# relay.net
KiCad netlist of a schematic drawn in EAGLE
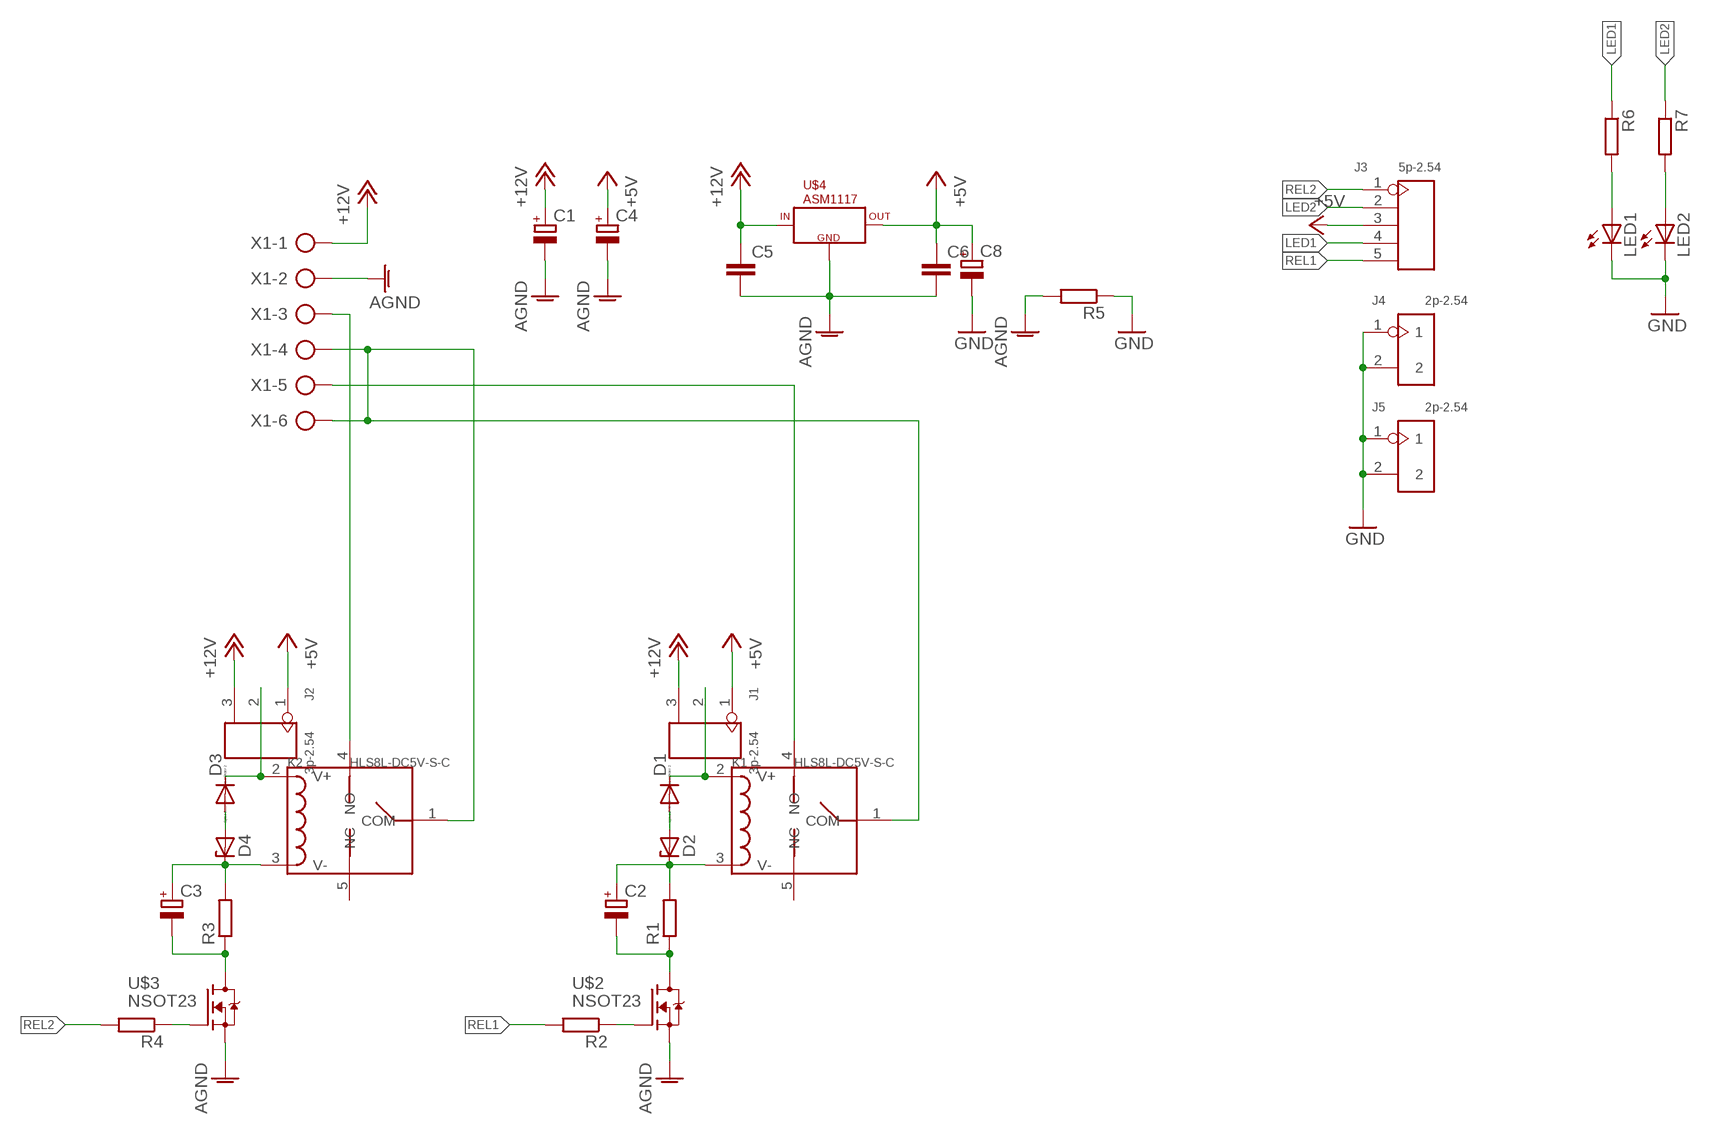
[diagram p0: schematic, sheet 1]

(export (version "E")
  (design (tool "Eeschema 10.0.6"))
  (components
    (comp (ref "C1")
      (value "CPOL-EU153CLV-0405")
      (footprint "eagle-import:153CLV-0405")
      (libsource (lib "eagle-import") (part "CPOL-EU153CLV-0405"))
    )
    (comp (ref "C2")
      (value "CPOL-EU153CLV-0405")
      (footprint "eagle-import:153CLV-0405")
      (libsource (lib "eagle-import") (part "CPOL-EU153CLV-0405"))
    )
    (comp (ref "C3")
      (value "CPOL-EU153CLV-0405")
      (footprint "eagle-import:153CLV-0405")
      (libsource (lib "eagle-import") (part "CPOL-EU153CLV-0405"))
    )
    (comp (ref "C4")
      (value "CPOL-EU153CLV-0405")
      (footprint "eagle-import:153CLV-0405")
      (libsource (lib "eagle-import") (part "CPOL-EU153CLV-0405"))
    )
    (comp (ref "C5")
      (value "C-EUC0805")
      (footprint "eagle-import:C0805")
      (libsource (lib "eagle-import") (part "C-EUC0805"))
    )
    (comp (ref "C6")
      (value "C-EUC0805")
      (footprint "eagle-import:C0805")
      (libsource (lib "eagle-import") (part "C-EUC0805"))
    )
    (comp (ref "C8")
      (value "CPOL-EUSMCD")
      (footprint "eagle-import:SMC_D")
      (libsource (lib "eagle-import") (part "CPOL-EUSMCD"))
    )
    (comp (ref "D1")
      (value "DIODE-MINIMELF")
      (footprint "eagle-import:MINIMELF")
      (libsource (lib "eagle-import") (part "DIODE-MINIMELF"))
    )
    (comp (ref "D2")
      (value "ZENER-DIODESOD80C")
      (footprint "eagle-import:SOD80C")
      (libsource (lib "eagle-import") (part "ZENER-DIODESOD80C"))
    )
    (comp (ref "D3")
      (value "DIODE-MINIMELF")
      (footprint "eagle-import:MINIMELF")
      (libsource (lib "eagle-import") (part "DIODE-MINIMELF"))
    )
    (comp (ref "D4")
      (value "ZENER-DIODESOD80C")
      (footprint "eagle-import:SOD80C")
      (libsource (lib "eagle-import") (part "ZENER-DIODESOD80C"))
    )
    (comp (ref "J1")
      (value "3p-2.54")
      (footprint "eagle-import:H3-2.54")
      (fields (field (name "MPN") "F185-1103A0BSYA1"))
      (libsource (lib "eagle-import") (part "DIP-BLACK-FEMALE-HEADER-VERT(3P-2.54)"))
    )
    (comp (ref "J2")
      (value "3p-2.54")
      (footprint "eagle-import:H3-2.54")
      (fields (field (name "MPN") "F185-1103A0BSYA1"))
      (libsource (lib "eagle-import") (part "DIP-BLACK-FEMALE-HEADER-VERT(3P-2.54)"))
    )
    (comp (ref "J3")
      (value "5p-2.54")
      (footprint "eagle-import:H5-2.54")
      (fields (field (name "MPN") "F185-1105A0BSYA1"))
      (libsource (lib "eagle-import") (part "DIP-BLACK-FEMALE-HEADER-VERT(5P-2.54)"))
    )
    (comp (ref "J4")
      (value "2p-2.54")
      (footprint "eagle-import:H2-2.54")
      (fields (field (name "MPN") "F185-1102A1BSYA1"))
      (libsource (lib "eagle-import") (part "DIP-BLACK-FEMALE-HEADER-VERT(2P-2.54)"))
    )
    (comp (ref "J5")
      (value "2p-2.54")
      (footprint "eagle-import:H2-2.54")
      (fields (field (name "MPN") "F185-1102A1BSYA1"))
      (libsource (lib "eagle-import") (part "DIP-BLACK-FEMALE-HEADER-VERT(2P-2.54)"))
    )
    (comp (ref "K1")
      (value "HLS8L-DC5V-S-C")
      (footprint "eagle-import:REY5-19.0X15.0X15.0MM")
      (libsource (lib "eagle-import") (part "RELAY-HLS8L-DC5V-S-C(5P-19X15MM)"))
    )
    (comp (ref "K2")
      (value "HLS8L-DC5V-S-C")
      (footprint "eagle-import:REY5-19.0X15.0X15.0MM")
      (libsource (lib "eagle-import") (part "RELAY-HLS8L-DC5V-S-C(5P-19X15MM)"))
    )
    (comp (ref "LED1")
      (value "LED5MM")
      (footprint "eagle-import:LED5MM")
      (libsource (lib "eagle-import") (part "LED5MM"))
    )
    (comp (ref "LED2")
      (value "LED5MM")
      (footprint "eagle-import:LED5MM")
      (libsource (lib "eagle-import") (part "LED5MM"))
    )
    (comp (ref "R1")
      (value "R-EU_R0805")
      (footprint "eagle-import:R0805")
      (libsource (lib "eagle-import") (part "R-EU_R0805"))
    )
    (comp (ref "R2")
      (value "R-EU_R0805")
      (footprint "eagle-import:R0805")
      (libsource (lib "eagle-import") (part "R-EU_R0805"))
    )
    (comp (ref "R3")
      (value "R-EU_R0805")
      (footprint "eagle-import:R0805")
      (libsource (lib "eagle-import") (part "R-EU_R0805"))
    )
    (comp (ref "R4")
      (value "R-EU_R0805")
      (footprint "eagle-import:R0805")
      (libsource (lib "eagle-import") (part "R-EU_R0805"))
    )
    (comp (ref "R5")
      (value "R-EU_R0805")
      (footprint "eagle-import:R0805")
      (libsource (lib "eagle-import") (part "R-EU_R0805"))
    )
    (comp (ref "R6")
      (value "R-EU_R0805")
      (footprint "eagle-import:R0805")
      (libsource (lib "eagle-import") (part "R-EU_R0805"))
    )
    (comp (ref "R7")
      (value "R-EU_R0805")
      (footprint "eagle-import:R0805")
      (libsource (lib "eagle-import") (part "R-EU_R0805"))
    )
    (comp (ref "U$2")
      (value "NSOT23")
      (footprint "eagle-import:SOT23W")
      (libsource (lib "eagle-import") (part "NSOT23"))
    )
    (comp (ref "U$3")
      (value "NSOT23")
      (footprint "eagle-import:SOT23W")
      (libsource (lib "eagle-import") (part "NSOT23"))
    )
    (comp (ref "U$4")
      (value "ASM1117")
      (footprint "eagle-import:SOT223")
      (libsource (lib "eagle-import") (part "ASM1117"))
    )
    (comp (ref "X1")
      (value "AK500/6-H")
      (footprint "eagle-import:AK500_6-H")
      (libsource (lib "eagle-import") (part "AK500/6-H"))
    )
  )
  (nets
    (net (code "1") (name "+5V") (class "Default")
      (node (ref "C4") (pin "+") (pinfunction "+_+") (pintype "passive"))
      (node (ref "C6") (pin "1") (pinfunction "1_1") (pintype "passive"))
      (node (ref "C8") (pin "+") (pinfunction "+_+") (pintype "passive"))
      (node (ref "J1") (pin "1") (pinfunction "P$1_1") (pintype "bidirectional"))
      (node (ref "J2") (pin "1") (pinfunction "P$1_1") (pintype "bidirectional"))
      (node (ref "J3") (pin "3") (pinfunction "3_3") (pintype "bidirectional"))
      (node (ref "U$4") (pin "2") (pinfunction "OUT_2") (pintype "power_in"))
      (node (ref "U$4") (pin "4") (pinfunction "OUT_4") (pintype "power_in"))
    )
    (net (code "2") (name "+12V") (class "Default")
      (node (ref "C1") (pin "+") (pinfunction "+_+") (pintype "passive"))
      (node (ref "C5") (pin "1") (pinfunction "1_1") (pintype "passive"))
      (node (ref "J1") (pin "3") (pinfunction "P$3_3") (pintype "bidirectional"))
      (node (ref "J2") (pin "3") (pinfunction "P$3_3") (pintype "bidirectional"))
      (node (ref "U$4") (pin "3") (pinfunction "IN_3") (pintype "power_in"))
      (node (ref "X1") (pin "1") (pinfunction "KL_1") (pintype "passive"))
    )
    (net (code "3") (name "AGND") (class "Default")
      (node (ref "C1") (pin "-") (pinfunction "-_-") (pintype "passive"))
      (node (ref "C4") (pin "-") (pinfunction "-_-") (pintype "passive"))
      (node (ref "C5") (pin "2") (pinfunction "2_2") (pintype "passive"))
      (node (ref "C6") (pin "2") (pinfunction "2_2") (pintype "passive"))
      (node (ref "R5") (pin "2") (pinfunction "2_2") (pintype "passive"))
      (node (ref "U$2") (pin "S") (pinfunction "S_S") (pintype "passive"))
      (node (ref "U$3") (pin "S") (pinfunction "S_S") (pintype "passive"))
      (node (ref "U$4") (pin "1") (pinfunction "GND_1") (pintype "power_in"))
      (node (ref "X1") (pin "2") (pinfunction "KL_2") (pintype "passive"))
    )
    (net (code "4") (name "GND") (class "Default")
      (node (ref "C8") (pin "-") (pinfunction "-_-") (pintype "passive"))
      (node (ref "J4") (pin "1") (pinfunction "1_1") (pintype "bidirectional"))
      (node (ref "J4") (pin "2") (pinfunction "2_2") (pintype "bidirectional"))
      (node (ref "J5") (pin "1") (pinfunction "1_1") (pintype "bidirectional"))
      (node (ref "J5") (pin "2") (pinfunction "2_2") (pintype "bidirectional"))
      (node (ref "LED1") (pin "K") (pinfunction "C_K") (pintype "passive"))
      (node (ref "LED2") (pin "K") (pinfunction "C_K") (pintype "passive"))
      (node (ref "R5") (pin "1") (pinfunction "1_1") (pintype "passive"))
    )
    (net (code "5") (name "LED1") (class "Default")
      (node (ref "J3") (pin "4") (pinfunction "4_4") (pintype "bidirectional"))
      (node (ref "R6") (pin "1") (pinfunction "1_1") (pintype "passive"))
    )
    (net (code "6") (name "LED2") (class "Default")
      (node (ref "J3") (pin "2") (pinfunction "2_2") (pintype "bidirectional"))
      (node (ref "R7") (pin "1") (pinfunction "1_1") (pintype "passive"))
    )
    (net (code "7") (name "Net-(C2-Pad-)") (class "Default")
      (node (ref "C2") (pin "-") (pinfunction "-_-") (pintype "passive"))
      (node (ref "R1") (pin "1") (pinfunction "1_1") (pintype "passive"))
      (node (ref "U$2") (pin "D") (pinfunction "D_D") (pintype "passive"))
    )
    (net (code "8") (name "Net-(C3-Pad-)") (class "Default")
      (node (ref "C3") (pin "-") (pinfunction "-_-") (pintype "passive"))
      (node (ref "R3") (pin "1") (pinfunction "1_1") (pintype "passive"))
      (node (ref "U$3") (pin "D") (pinfunction "D_D") (pintype "passive"))
    )
    (net (code "9") (name "Net-(D1-PadA)") (class "Default")
      (node (ref "D1") (pin "A") (pinfunction "A_A") (pintype "passive"))
      (node (ref "D2") (pin "A") (pinfunction "A_A") (pintype "passive"))
    )
    (net (code "10") (name "Net-(D3-PadA)") (class "Default")
      (node (ref "D3") (pin "A") (pinfunction "A_A") (pintype "passive"))
      (node (ref "D4") (pin "A") (pinfunction "A_A") (pintype "passive"))
    )
    (net (code "11") (name "Net-(J1-P$2)") (class "Default")
      (node (ref "D1") (pin "C") (pinfunction "C_C") (pintype "passive"))
      (node (ref "J1") (pin "2") (pinfunction "P$2_2") (pintype "bidirectional"))
      (node (ref "K1") (pin "2") (pinfunction "V+_2") (pintype "bidirectional"))
    )
    (net (code "12") (name "Net-(J2-P$2)") (class "Default")
      (node (ref "D3") (pin "C") (pinfunction "C_C") (pintype "passive"))
      (node (ref "J2") (pin "2") (pinfunction "P$2_2") (pintype "bidirectional"))
      (node (ref "K2") (pin "2") (pinfunction "V+_2") (pintype "bidirectional"))
    )
    (net (code "13") (name "Net-(K1-COM)") (class "Default")
      (node (ref "K1") (pin "1") (pinfunction "COM_1") (pintype "bidirectional"))
      (node (ref "K2") (pin "1") (pinfunction "COM_1") (pintype "bidirectional"))
      (node (ref "X1") (pin "4") (pinfunction "KL_4") (pintype "passive"))
      (node (ref "X1") (pin "6") (pinfunction "KL_6") (pintype "passive"))
    )
    (net (code "14") (name "Net-(K1-NO)") (class "Default")
      (node (ref "K1") (pin "4") (pinfunction "NO_4") (pintype "bidirectional"))
      (node (ref "X1") (pin "5") (pinfunction "KL_5") (pintype "passive"))
    )
    (net (code "15") (name "Net-(K1-V-)") (class "Default")
      (node (ref "C2") (pin "+") (pinfunction "+_+") (pintype "passive"))
      (node (ref "D2") (pin "C") (pinfunction "C_C") (pintype "passive"))
      (node (ref "K1") (pin "3") (pinfunction "V-_3") (pintype "bidirectional"))
      (node (ref "R1") (pin "2") (pinfunction "2_2") (pintype "passive"))
    )
    (net (code "16") (name "Net-(K2-NO)") (class "Default")
      (node (ref "K2") (pin "4") (pinfunction "NO_4") (pintype "bidirectional"))
      (node (ref "X1") (pin "3") (pinfunction "KL_3") (pintype "passive"))
    )
    (net (code "17") (name "Net-(K2-V-)") (class "Default")
      (node (ref "C3") (pin "+") (pinfunction "+_+") (pintype "passive"))
      (node (ref "D4") (pin "C") (pinfunction "C_C") (pintype "passive"))
      (node (ref "K2") (pin "3") (pinfunction "V-_3") (pintype "bidirectional"))
      (node (ref "R3") (pin "2") (pinfunction "2_2") (pintype "passive"))
    )
    (net (code "18") (name "Net-(LED1-PadA)") (class "Default")
      (node (ref "LED1") (pin "A") (pinfunction "A_A") (pintype "passive"))
      (node (ref "R6") (pin "2") (pinfunction "2_2") (pintype "passive"))
    )
    (net (code "19") (name "Net-(LED2-PadA)") (class "Default")
      (node (ref "LED2") (pin "A") (pinfunction "A_A") (pintype "passive"))
      (node (ref "R7") (pin "2") (pinfunction "2_2") (pintype "passive"))
    )
    (net (code "20") (name "Net-(R2-Pad1)") (class "Default")
      (node (ref "R2") (pin "1") (pinfunction "1_1") (pintype "passive"))
      (node (ref "U$2") (pin "G") (pinfunction "G_G") (pintype "passive"))
    )
    (net (code "21") (name "Net-(R4-Pad1)") (class "Default")
      (node (ref "R4") (pin "1") (pinfunction "1_1") (pintype "passive"))
      (node (ref "U$3") (pin "G") (pinfunction "G_G") (pintype "passive"))
    )
    (net (code "22") (name "REL1") (class "Default")
      (node (ref "J3") (pin "5") (pinfunction "5_5") (pintype "bidirectional"))
      (node (ref "R2") (pin "2") (pinfunction "2_2") (pintype "passive"))
    )
    (net (code "23") (name "REL2") (class "Default")
      (node (ref "J3") (pin "1") (pinfunction "1_1") (pintype "bidirectional"))
      (node (ref "R4") (pin "2") (pinfunction "2_2") (pintype "passive"))
    )
    (net (code "24") (name "unconnected-(K1-NC-Pad5)") (class "Default")
      (node (ref "K1") (pin "5") (pinfunction "NC_5") (pintype "bidirectional"))
    )
    (net (code "25") (name "unconnected-(K2-NC-Pad5)") (class "Default")
      (node (ref "K2") (pin "5") (pinfunction "NC_5") (pintype "bidirectional"))
    )
  )
)
